# 3V3_LDO.net
KiCad netlist of a schematic drawn in Altium Designer
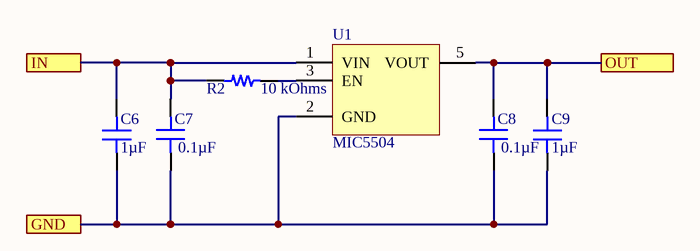
[diagram p0: 3V3_LDO.SchDoc]

(export (version "E")
  (design (tool "Eeschema 10.0.6"))
  (components
    (comp (ref "C6")
      (value "1µF")
      (footprint "CAP 0603_1608")
      (description "CAP CER 1UF 25V X7R 0603")
      (fields
        (field (name "PART NUMBER") "GCJ188R71E105KA01D")
        (field (name "MANUFACTURER") "Murata Electronics")
      )
      (libsource (lib "Celestial Altium Library - altium_library") (part "Capacitor"))
    )
    (comp (ref "C7")
      (value "0.1µF")
      (footprint "CAP 0603_1608")
      (description "CAP CER 0.1UF 100V 0603 EPOXY")
      (fields
        (field (name "PART NUMBER") "GCG188R92A104KA03D")
        (field (name "MANUFACTURER") "Murata Electronics")
      )
      (libsource (lib "Celestial Altium Library - altium_library") (part "Capacitor"))
    )
    (comp (ref "C8")
      (value "0.1µF")
      (footprint "CAP 0603_1608")
      (description "CAP CER 0.1UF 100V 0603 EPOXY")
      (fields
        (field (name "PART NUMBER") "GCG188R92A104KA03D")
        (field (name "MANUFACTURER") "Murata Electronics")
      )
      (libsource (lib "Celestial Altium Library - altium_library") (part "Capacitor"))
    )
    (comp (ref "C9")
      (value "1µF")
      (footprint "CAP 0603_1608")
      (description "CAP CER 1UF 25V X7R 0603")
      (fields
        (field (name "PART NUMBER") "GCJ188R71E105KA01D")
        (field (name "MANUFACTURER") "Murata Electronics")
      )
      (libsource (lib "Celestial Altium Library - altium_library") (part "Capacitor"))
    )
    (comp (ref "R2")
      (value "10 kOhms")
      (footprint "RES 0603_1608")
      (description "RES 10K OHM 0.1% 1/16W 0603")
      (fields
        (field (name "PART NUMBER") "RNCS0603BKE10K0")
        (field (name "MANUFACTURER") "Stackpole Electronics Inc")
      )
      (libsource (lib "Celestial Altium Library - altium_library") (part "Resistor"))
    )
    (comp (ref "U1")
      (value "MIC5504")
      (footprint "TI SOT-23-5 DBV")
      (description "3.3V LDO")
      (libsource (lib "IC") (part "MIC5504-3.3YM5"))
    )
  )
  (nets
    (net (code "1") (name "/GND") (class "Default")
      (node (ref "C6") (pin "1") (pinfunction "1_1") (pintype "passive"))
      (node (ref "C7") (pin "2") (pinfunction "2_2") (pintype "passive"))
      (node (ref "C8") (pin "2") (pinfunction "2_2") (pintype "passive"))
      (node (ref "C9") (pin "1") (pinfunction "1_1") (pintype "passive"))
      (node (ref "U1") (pin "2") (pinfunction "GND_2") (pintype "passive"))
    )
    (net (code "2") (name "/IN") (class "Default")
      (node (ref "C6") (pin "2") (pinfunction "2_2") (pintype "passive"))
      (node (ref "C7") (pin "1") (pinfunction "1_1") (pintype "passive"))
      (node (ref "R2") (pin "2") (pinfunction "2_2") (pintype "passive"))
      (node (ref "U1") (pin "1") (pinfunction "VIN_1") (pintype "passive"))
    )
    (net (code "3") (name "/OUT") (class "Default")
      (node (ref "C8") (pin "1") (pinfunction "1_1") (pintype "passive"))
      (node (ref "C9") (pin "2") (pinfunction "2_2") (pintype "passive"))
      (node (ref "U1") (pin "5") (pinfunction "VOUT_5") (pintype "passive"))
    )
    (net (code "4") (name "Net-(U1-EN)") (class "Default")
      (node (ref "R2") (pin "1") (pinfunction "1_1") (pintype "passive"))
      (node (ref "U1") (pin "3") (pinfunction "EN_3") (pintype "passive"))
    )
  )
)
